# autolock.net
KiCad netlist of a schematic drawn in EAGLE
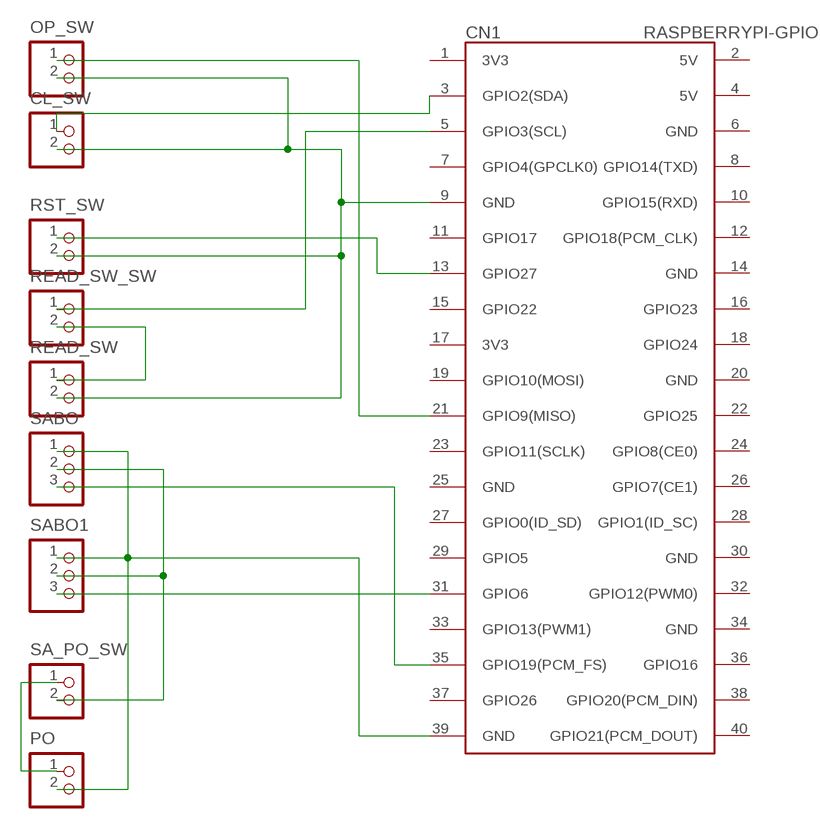
[diagram p0: schematic, sheet 1]

(export (version "E")
  (design (tool "Eeschema 10.0.6"))
  (components
    (comp (ref "CL_SW")
      (value "B2B-XH-A")
      (footprint "eagle-import:B2B-XH-A")
      (libsource (lib "eagle-import") (part "B2B-XH-A"))
    )
    (comp (ref "CN1")
      (value "RASPBERRYPI-GPIO")
      (footprint "eagle-import:2X20-BOLD")
      (libsource (lib "eagle-import") (part "RASPBERRYPI-GPIO"))
    )
    (comp (ref "OP_SW")
      (value "B2B-XH-A")
      (footprint "eagle-import:B2B-XH-A")
      (libsource (lib "eagle-import") (part "B2B-XH-A"))
    )
    (comp (ref "PO")
      (value "B2B-XH-A")
      (footprint "eagle-import:B2B-XH-A")
      (libsource (lib "eagle-import") (part "B2B-XH-A"))
    )
    (comp (ref "READ_SW")
      (value "B2B-XH-A")
      (footprint "eagle-import:B2B-XH-A")
      (libsource (lib "eagle-import") (part "B2B-XH-A"))
    )
    (comp (ref "READ_SW_SW")
      (value "B2B-XH-A")
      (footprint "eagle-import:B2B-XH-A")
      (libsource (lib "eagle-import") (part "B2B-XH-A"))
    )
    (comp (ref "RST_SW")
      (value "B2B-XH-A")
      (footprint "eagle-import:B2B-XH-A")
      (libsource (lib "eagle-import") (part "B2B-XH-A"))
    )
    (comp (ref "SABO")
      (value "B3B-XH-A")
      (footprint "eagle-import:B3B-XH-A")
      (libsource (lib "eagle-import") (part "B3B-XH-A"))
    )
    (comp (ref "SABO1")
      (value "B3B-XH-A")
      (footprint "eagle-import:B3B-XH-A")
      (libsource (lib "eagle-import") (part "B3B-XH-A"))
    )
    (comp (ref "SA_PO_SW")
      (value "B2B-XH-A")
      (footprint "eagle-import:B2B-XH-A")
      (libsource (lib "eagle-import") (part "B2B-XH-A"))
    )
  )
  (nets
    (net (code "1") (name "/GND") (class "Default")
      (node (ref "CL_SW") (pin "2") (pinfunction "2_2") (pintype "passive"))
      (node (ref "CN1") (pin "39") (pinfunction "GND_39") (pintype "bidirectional"))
      (node (ref "CN1") (pin "9") (pinfunction "GND_9") (pintype "bidirectional"))
      (node (ref "OP_SW") (pin "2") (pinfunction "2_2") (pintype "passive"))
      (node (ref "PO") (pin "2") (pinfunction "2_2") (pintype "passive"))
      (node (ref "READ_SW") (pin "2") (pinfunction "2_2") (pintype "passive"))
      (node (ref "RST_SW") (pin "2") (pinfunction "2_2") (pintype "passive"))
      (node (ref "SABO") (pin "1") (pinfunction "1_1") (pintype "passive"))
      (node (ref "SABO1") (pin "1") (pinfunction "1_1") (pintype "passive"))
    )
    (net (code "2") (name "Net-(CN1-GPIO2(SDA))") (class "Default")
      (node (ref "CL_SW") (pin "1") (pinfunction "1_1") (pintype "passive"))
      (node (ref "CN1") (pin "3") (pinfunction "GPIO2(SDA)_3") (pintype "bidirectional"))
    )
    (net (code "3") (name "Net-(CN1-GPIO3(SCL))") (class "Default")
      (node (ref "CN1") (pin "5") (pinfunction "GPIO3(SCL)_5") (pintype "bidirectional"))
      (node (ref "READ_SW_SW") (pin "1") (pinfunction "1_1") (pintype "passive"))
    )
    (net (code "4") (name "Net-(CN1-GPIO6)") (class "Default")
      (node (ref "CN1") (pin "31") (pinfunction "GPIO6_31") (pintype "bidirectional"))
      (node (ref "SABO1") (pin "3") (pinfunction "3_3") (pintype "passive"))
    )
    (net (code "5") (name "Net-(CN1-GPIO9(MISO))") (class "Default")
      (node (ref "CN1") (pin "21") (pinfunction "GPIO9(MISO)_21") (pintype "bidirectional"))
      (node (ref "OP_SW") (pin "1") (pinfunction "1_1") (pintype "passive"))
    )
    (net (code "6") (name "Net-(CN1-GPIO19(PCM_FS))") (class "Default")
      (node (ref "CN1") (pin "35") (pinfunction "GPIO19(PCM_FS)_35") (pintype "bidirectional"))
      (node (ref "SABO") (pin "3") (pinfunction "3_3") (pintype "passive"))
    )
    (net (code "7") (name "Net-(CN1-GPIO27)") (class "Default")
      (node (ref "CN1") (pin "13") (pinfunction "GPIO27_13") (pintype "bidirectional"))
      (node (ref "RST_SW") (pin "1") (pinfunction "1_1") (pintype "passive"))
    )
    (net (code "8") (name "Net-(PO-Pad1)") (class "Default")
      (node (ref "PO") (pin "1") (pinfunction "1_1") (pintype "passive"))
      (node (ref "SA_PO_SW") (pin "1") (pinfunction "1_1") (pintype "passive"))
    )
    (net (code "9") (name "Net-(READ_SW-Pad1)") (class "Default")
      (node (ref "READ_SW") (pin "1") (pinfunction "1_1") (pintype "passive"))
      (node (ref "READ_SW_SW") (pin "2") (pinfunction "2_2") (pintype "passive"))
    )
    (net (code "10") (name "Net-(SABO-Pad2)") (class "Default")
      (node (ref "SABO") (pin "2") (pinfunction "2_2") (pintype "passive"))
      (node (ref "SABO1") (pin "2") (pinfunction "2_2") (pintype "passive"))
      (node (ref "SA_PO_SW") (pin "2") (pinfunction "2_2") (pintype "passive"))
    )
    (net (code "11") (name "unconnected-(CN1-3V3-Pad1)") (class "Default")
      (node (ref "CN1") (pin "1") (pinfunction "3V3_1") (pintype "bidirectional"))
    )
    (net (code "12") (name "unconnected-(CN1-3V3-Pad17)") (class "Default")
      (node (ref "CN1") (pin "17") (pinfunction "3V3_17") (pintype "bidirectional"))
    )
    (net (code "13") (name "unconnected-(CN1-5V-Pad2)") (class "Default")
      (node (ref "CN1") (pin "2") (pinfunction "5V_2") (pintype "bidirectional"))
    )
    (net (code "14") (name "unconnected-(CN1-5V-Pad4)") (class "Default")
      (node (ref "CN1") (pin "4") (pinfunction "5V_4") (pintype "bidirectional"))
    )
    (net (code "15") (name "unconnected-(CN1-GND-Pad6)") (class "Default")
      (node (ref "CN1") (pin "6") (pinfunction "GND_6") (pintype "bidirectional"))
    )
    (net (code "16") (name "unconnected-(CN1-GND-Pad14)") (class "Default")
      (node (ref "CN1") (pin "14") (pinfunction "GND_14") (pintype "bidirectional"))
    )
    (net (code "17") (name "unconnected-(CN1-GND-Pad20)") (class "Default")
      (node (ref "CN1") (pin "20") (pinfunction "GND_20") (pintype "bidirectional"))
    )
    (net (code "18") (name "unconnected-(CN1-GND-Pad25)") (class "Default")
      (node (ref "CN1") (pin "25") (pinfunction "GND_25") (pintype "bidirectional"))
    )
    (net (code "19") (name "unconnected-(CN1-GND-Pad30)") (class "Default")
      (node (ref "CN1") (pin "30") (pinfunction "GND_30") (pintype "bidirectional"))
    )
    (net (code "20") (name "unconnected-(CN1-GND-Pad34)") (class "Default")
      (node (ref "CN1") (pin "34") (pinfunction "GND_34") (pintype "bidirectional"))
    )
    (net (code "21") (name "unconnected-(CN1-GPIO0(ID_SD)-Pad27)") (class "Default")
      (node (ref "CN1") (pin "27") (pinfunction "GPIO0(ID_SD)_27") (pintype "bidirectional"))
    )
    (net (code "22") (name "unconnected-(CN1-GPIO1(ID_SC)-Pad28)") (class "Default")
      (node (ref "CN1") (pin "28") (pinfunction "GPIO1(ID_SC)_28") (pintype "bidirectional"))
    )
    (net (code "23") (name "unconnected-(CN1-GPIO4(GPCLK0)-Pad7)") (class "Default")
      (node (ref "CN1") (pin "7") (pinfunction "GPIO4(GPCLK0)_7") (pintype "bidirectional"))
    )
    (net (code "24") (name "unconnected-(CN1-GPIO5-Pad29)") (class "Default")
      (node (ref "CN1") (pin "29") (pinfunction "GPIO5_29") (pintype "bidirectional"))
    )
    (net (code "25") (name "unconnected-(CN1-GPIO7(CE1)-Pad26)") (class "Default")
      (node (ref "CN1") (pin "26") (pinfunction "GPIO7(CE1)_26") (pintype "bidirectional"))
    )
    (net (code "26") (name "unconnected-(CN1-GPIO8(CE0)-Pad24)") (class "Default")
      (node (ref "CN1") (pin "24") (pinfunction "GPIO8(CE0)_24") (pintype "bidirectional"))
    )
    (net (code "27") (name "unconnected-(CN1-GPIO10(MOSI)-Pad19)") (class "Default")
      (node (ref "CN1") (pin "19") (pinfunction "GPIO10(MOSI)_19") (pintype "bidirectional"))
    )
    (net (code "28") (name "unconnected-(CN1-GPIO11(SCLK)-Pad23)") (class "Default")
      (node (ref "CN1") (pin "23") (pinfunction "GPIO11(SCLK)_23") (pintype "bidirectional"))
    )
    (net (code "29") (name "unconnected-(CN1-GPIO12(PWM0)-Pad32)") (class "Default")
      (node (ref "CN1") (pin "32") (pinfunction "GPIO12(PWM0)_32") (pintype "bidirectional"))
    )
    (net (code "30") (name "unconnected-(CN1-GPIO13(PWM1)-Pad33)") (class "Default")
      (node (ref "CN1") (pin "33") (pinfunction "GPIO13(PWM1)_33") (pintype "bidirectional"))
    )
    (net (code "31") (name "unconnected-(CN1-GPIO14(TXD)-Pad8)") (class "Default")
      (node (ref "CN1") (pin "8") (pinfunction "GPIO14(TXD)_8") (pintype "bidirectional"))
    )
    (net (code "32") (name "unconnected-(CN1-GPIO15(RXD)-Pad10)") (class "Default")
      (node (ref "CN1") (pin "10") (pinfunction "GPIO15(RXD)_10") (pintype "bidirectional"))
    )
    (net (code "33") (name "unconnected-(CN1-GPIO16-Pad36)") (class "Default")
      (node (ref "CN1") (pin "36") (pinfunction "GPIO16_36") (pintype "bidirectional"))
    )
    (net (code "34") (name "unconnected-(CN1-GPIO17-Pad11)") (class "Default")
      (node (ref "CN1") (pin "11") (pinfunction "GPIO17_11") (pintype "bidirectional"))
    )
    (net (code "35") (name "unconnected-(CN1-GPIO18(PCM_CLK)-Pad12)") (class "Default")
      (node (ref "CN1") (pin "12") (pinfunction "GPIO18(PCM_CLK)_12") (pintype "bidirectional"))
    )
    (net (code "36") (name "unconnected-(CN1-GPIO20(PCM_DIN)-Pad38)") (class "Default")
      (node (ref "CN1") (pin "38") (pinfunction "GPIO20(PCM_DIN)_38") (pintype "bidirectional"))
    )
    (net (code "37") (name "unconnected-(CN1-GPIO21(PCM_DOUT)-Pad40)") (class "Default")
      (node (ref "CN1") (pin "40") (pinfunction "GPIO21(PCM_DOUT)_40") (pintype "bidirectional"))
    )
    (net (code "38") (name "unconnected-(CN1-GPIO22-Pad15)") (class "Default")
      (node (ref "CN1") (pin "15") (pinfunction "GPIO22_15") (pintype "bidirectional"))
    )
    (net (code "39") (name "unconnected-(CN1-GPIO23-Pad16)") (class "Default")
      (node (ref "CN1") (pin "16") (pinfunction "GPIO23_16") (pintype "bidirectional"))
    )
    (net (code "40") (name "unconnected-(CN1-GPIO24-Pad18)") (class "Default")
      (node (ref "CN1") (pin "18") (pinfunction "GPIO24_18") (pintype "bidirectional"))
    )
    (net (code "41") (name "unconnected-(CN1-GPIO25-Pad22)") (class "Default")
      (node (ref "CN1") (pin "22") (pinfunction "GPIO25_22") (pintype "bidirectional"))
    )
    (net (code "42") (name "unconnected-(CN1-GPIO26-Pad37)") (class "Default")
      (node (ref "CN1") (pin "37") (pinfunction "GPIO26_37") (pintype "bidirectional"))
    )
  )
)
